# LEDdriverSFE_CREE_02.net
KiCad netlist of a schematic drawn in EAGLE
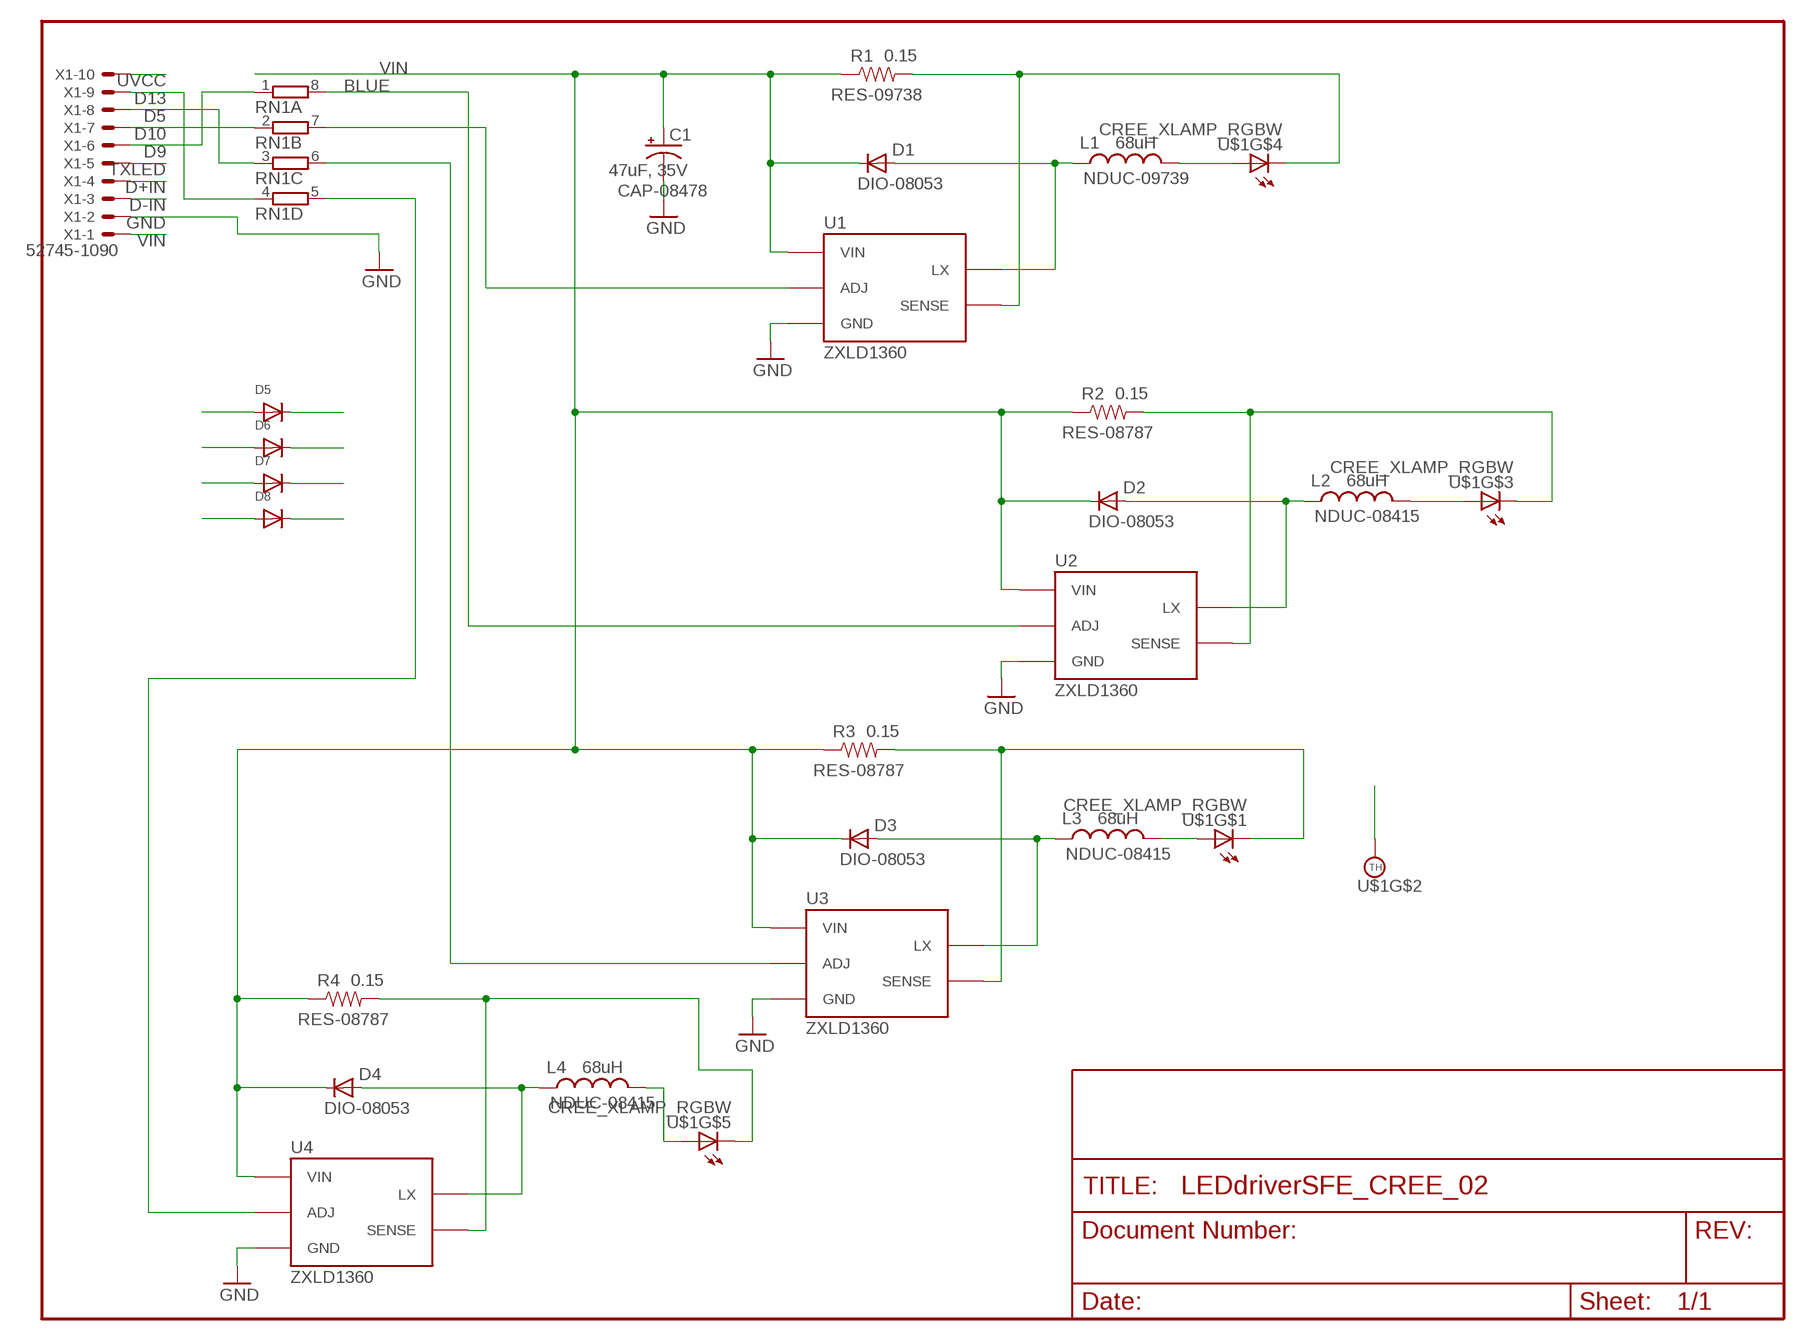
[diagram p0: schematic, sheet 1]

(export (version "E")
  (design (tool "Eeschema 10.0.6"))
  (components
    (comp (ref "C1")
      (value "47uF, 35V")
      (footprint "eagle-import:PANASONIC_D")
      (libsource (lib "eagle-import") (part "CAP_POLD"))
    )
    (comp (ref "D1")
      (value "MBRA140")
      (footprint "eagle-import:SMA-DIODE")
      (libsource (lib "eagle-import") (part "DIODESMA"))
    )
    (comp (ref "D2")
      (value "MBRA140")
      (footprint "eagle-import:SMA-DIODE")
      (libsource (lib "eagle-import") (part "DIODESMA"))
    )
    (comp (ref "D3")
      (value "MBRA140")
      (footprint "eagle-import:SMA-DIODE")
      (libsource (lib "eagle-import") (part "DIODESMA"))
    )
    (comp (ref "D4")
      (value "MBRA140")
      (footprint "eagle-import:SMA-DIODE")
      (libsource (lib "eagle-import") (part "DIODESMA"))
    )
    (comp (ref "D5")
      (value "DIODESOD-323F")
      (footprint "eagle-import:SOD-323F")
      (libsource (lib "eagle-import") (part "DIODESOD-323F"))
    )
    (comp (ref "D6")
      (value "DIODESOD-323F")
      (footprint "eagle-import:SOD-323F")
      (libsource (lib "eagle-import") (part "DIODESOD-323F"))
    )
    (comp (ref "D7")
      (value "DIODESOD-323F")
      (footprint "eagle-import:SOD-323F")
      (libsource (lib "eagle-import") (part "DIODESOD-323F"))
    )
    (comp (ref "D8")
      (value "DIODESOD-323F")
      (footprint "eagle-import:SOD-323F")
      (libsource (lib "eagle-import") (part "DIODESOD-323F"))
    )
    (comp (ref "L1")
      (value "68uH")
      (footprint "eagle-import:TDK6045")
      (libsource (lib "eagle-import") (part "L-US"))
    )
    (comp (ref "L2")
      (value "68uH")
      (footprint "eagle-import:TDK6045")
      (libsource (lib "eagle-import") (part "L-US"))
    )
    (comp (ref "L3")
      (value "68uH")
      (footprint "eagle-import:TDK6045")
      (libsource (lib "eagle-import") (part "L-US"))
    )
    (comp (ref "L4")
      (value "68uH")
      (footprint "eagle-import:TDK6045")
      (libsource (lib "eagle-import") (part "L-US"))
    )
    (comp (ref "R1")
      (value "0.15")
      (footprint "eagle-import:0603-RES")
      (libsource (lib "eagle-import") (part "RESISTOR0603-RES"))
    )
    (comp (ref "R2")
      (value "0.15")
      (footprint "eagle-import:0603-RES")
      (libsource (lib "eagle-import") (part "RESISTOR0603-RES"))
    )
    (comp (ref "R3")
      (value "0.15")
      (footprint "eagle-import:0603-RES")
      (libsource (lib "eagle-import") (part "RESISTOR0603-RES"))
    )
    (comp (ref "R4")
      (value "0.15")
      (footprint "eagle-import:0603-RES")
      (libsource (lib "eagle-import") (part "RESISTOR0603-RES"))
    )
    (comp (ref "RN1")
      (value "4R-NEXBV8V")
      (footprint "eagle-import:EXBV8V")
      (libsource (lib "eagle-import") (part "4R-NEXBV8V"))
    )
    (comp (ref "U$1")
      (value "CREE_XLAMP_RGBW")
      (footprint "eagle-import:CREE_XLAMP_XML")
      (libsource (lib "eagle-import") (part "CREE_XLAMP_RGBW"))
    )
    (comp (ref "U1")
      (value "ZXLD1360")
      (footprint "eagle-import:SOT23-5")
      (libsource (lib "eagle-import") (part "ZXLD1360"))
    )
    (comp (ref "U2")
      (value "ZXLD1360")
      (footprint "eagle-import:SOT23-5")
      (libsource (lib "eagle-import") (part "ZXLD1360"))
    )
    (comp (ref "U3")
      (value "ZXLD1360")
      (footprint "eagle-import:SOT23-5")
      (libsource (lib "eagle-import") (part "ZXLD1360"))
    )
    (comp (ref "U4")
      (value "ZXLD1360")
      (footprint "eagle-import:SOT23-5")
      (libsource (lib "eagle-import") (part "ZXLD1360"))
    )
    (comp (ref "X1")
      (value "52745-1090")
      (footprint "eagle-import:52745-1090")
      (libsource (lib "eagle-import") (part "52745-1090"))
    )
  )
  (nets
    (net (code "1") (name "/BLUE") (class "Default")
      (node (ref "RN1") (pin "8") (pinfunction "2_8") (pintype "passive"))
      (node (ref "U2") (pin "3") (pinfunction "ADJ_3") (pintype "bidirectional"))
    )
    (net (code "2") (name "/D+IN") (class "Default")
      (node (ref "X1") (pin "4") (pinfunction "S_4") (pintype "passive"))
    )
    (net (code "3") (name "/D-IN") (class "Default")
      (node (ref "X1") (pin "3") (pinfunction "S_3") (pintype "passive"))
    )
    (net (code "4") (name "/D5") (class "Default")
      (node (ref "D8") (pin "C") (pinfunction "C_C") (pintype "passive"))
      (node (ref "RN1") (pin "3") (pinfunction "1_3") (pintype "passive"))
      (node (ref "X1") (pin "8") (pinfunction "S_8") (pintype "passive"))
    )
    (net (code "5") (name "/D9") (class "Default")
      (node (ref "D5") (pin "C") (pinfunction "C_C") (pintype "passive"))
      (node (ref "RN1") (pin "1") (pinfunction "1_1") (pintype "passive"))
      (node (ref "X1") (pin "6") (pinfunction "S_6") (pintype "passive"))
    )
    (net (code "6") (name "/D10") (class "Default")
      (node (ref "D6") (pin "C") (pinfunction "C_C") (pintype "passive"))
      (node (ref "RN1") (pin "2") (pinfunction "1_2") (pintype "passive"))
      (node (ref "X1") (pin "7") (pinfunction "S_7") (pintype "passive"))
    )
    (net (code "7") (name "/D13") (class "Default")
      (node (ref "D7") (pin "C") (pinfunction "C_C") (pintype "passive"))
      (node (ref "RN1") (pin "4") (pinfunction "1_4") (pintype "passive"))
      (node (ref "X1") (pin "9") (pinfunction "S_9") (pintype "passive"))
    )
    (net (code "8") (name "/TXLED") (class "Default")
      (node (ref "X1") (pin "5") (pinfunction "S_5") (pintype "passive"))
    )
    (net (code "9") (name "/UVCC") (class "Default")
      (node (ref "X1") (pin "10") (pinfunction "S_10") (pintype "passive"))
    )
    (net (code "10") (name "/VIN") (class "Default")
      (node (ref "C1") (pin "+") (pinfunction "+_+") (pintype "passive"))
      (node (ref "D1") (pin "C") (pinfunction "C_C") (pintype "passive"))
      (node (ref "D2") (pin "C") (pinfunction "C_C") (pintype "passive"))
      (node (ref "D3") (pin "C") (pinfunction "C_C") (pintype "passive"))
      (node (ref "D4") (pin "C") (pinfunction "C_C") (pintype "passive"))
      (node (ref "R1") (pin "1") (pinfunction "1_1") (pintype "passive"))
      (node (ref "R2") (pin "1") (pinfunction "1_1") (pintype "passive"))
      (node (ref "R3") (pin "1") (pinfunction "1_1") (pintype "passive"))
      (node (ref "R4") (pin "1") (pinfunction "1_1") (pintype "passive"))
      (node (ref "U1") (pin "5") (pinfunction "VIN_5") (pintype "bidirectional"))
      (node (ref "U2") (pin "5") (pinfunction "VIN_5") (pintype "bidirectional"))
      (node (ref "U3") (pin "5") (pinfunction "VIN_5") (pintype "bidirectional"))
      (node (ref "U4") (pin "5") (pinfunction "VIN_5") (pintype "bidirectional"))
      (node (ref "X1") (pin "1") (pinfunction "S_1") (pintype "passive"))
    )
    (net (code "11") (name "GND") (class "Default")
      (node (ref "C1") (pin "-") (pinfunction "-_-") (pintype "passive"))
      (node (ref "D5") (pin "A") (pinfunction "A_A") (pintype "passive"))
      (node (ref "D6") (pin "A") (pinfunction "A_A") (pintype "passive"))
      (node (ref "D7") (pin "A") (pinfunction "A_A") (pintype "passive"))
      (node (ref "D8") (pin "A") (pinfunction "A_A") (pintype "passive"))
      (node (ref "U1") (pin "2") (pinfunction "GND_2") (pintype "bidirectional"))
      (node (ref "U2") (pin "2") (pinfunction "GND_2") (pintype "bidirectional"))
      (node (ref "U3") (pin "2") (pinfunction "GND_2") (pintype "bidirectional"))
      (node (ref "U4") (pin "2") (pinfunction "GND_2") (pintype "bidirectional"))
      (node (ref "X1") (pin "2") (pinfunction "S_2") (pintype "passive"))
    )
    (net (code "12") (name "Net-(RN1B-2)") (class "Default")
      (node (ref "RN1") (pin "7") (pinfunction "2_7") (pintype "passive"))
      (node (ref "U1") (pin "3") (pinfunction "ADJ_3") (pintype "bidirectional"))
    )
    (net (code "13") (name "Net-(RN1C-2)") (class "Default")
      (node (ref "RN1") (pin "6") (pinfunction "2_6") (pintype "passive"))
      (node (ref "U3") (pin "3") (pinfunction "ADJ_3") (pintype "bidirectional"))
    )
    (net (code "14") (name "Net-(RN1D-2)") (class "Default")
      (node (ref "RN1") (pin "5") (pinfunction "2_5") (pintype "passive"))
      (node (ref "U4") (pin "3") (pinfunction "ADJ_3") (pintype "bidirectional"))
    )
    (net (code "15") (name "Net-(U$1A-A)") (class "Default")
      (node (ref "L3") (pin "2") (pinfunction "2_2") (pintype "passive"))
      (node (ref "U$1") (pin "1") (pinfunction "A_1") (pintype "passive"))
    )
    (net (code "16") (name "Net-(U$1A-C)") (class "Default")
      (node (ref "R3") (pin "2") (pinfunction "2_2") (pintype "passive"))
      (node (ref "U$1") (pin "8") (pinfunction "C_8") (pintype "passive"))
      (node (ref "U3") (pin "4") (pinfunction "SENSE_4") (pintype "bidirectional"))
    )
    (net (code "17") (name "Net-(U$1C-A)") (class "Default")
      (node (ref "L2") (pin "2") (pinfunction "2_2") (pintype "passive"))
      (node (ref "U$1") (pin "2") (pinfunction "A_2") (pintype "passive"))
    )
    (net (code "18") (name "Net-(U$1C-C)") (class "Default")
      (node (ref "R2") (pin "2") (pinfunction "2_2") (pintype "passive"))
      (node (ref "U$1") (pin "7") (pinfunction "C_7") (pintype "passive"))
      (node (ref "U2") (pin "4") (pinfunction "SENSE_4") (pintype "bidirectional"))
    )
    (net (code "19") (name "Net-(U$1D-A)") (class "Default")
      (node (ref "L1") (pin "2") (pinfunction "2_2") (pintype "passive"))
      (node (ref "U$1") (pin "3") (pinfunction "A_3") (pintype "passive"))
    )
    (net (code "20") (name "Net-(U$1D-C)") (class "Default")
      (node (ref "R1") (pin "2") (pinfunction "2_2") (pintype "passive"))
      (node (ref "U$1") (pin "6") (pinfunction "C_6") (pintype "passive"))
      (node (ref "U1") (pin "4") (pinfunction "SENSE_4") (pintype "bidirectional"))
    )
    (net (code "21") (name "Net-(U$1E-A)") (class "Default")
      (node (ref "L4") (pin "2") (pinfunction "2_2") (pintype "passive"))
      (node (ref "U$1") (pin "4") (pinfunction "A_4") (pintype "passive"))
    )
    (net (code "22") (name "Net-(U$1E-C)") (class "Default")
      (node (ref "R4") (pin "2") (pinfunction "2_2") (pintype "passive"))
      (node (ref "U$1") (pin "5") (pinfunction "C_5") (pintype "passive"))
      (node (ref "U4") (pin "4") (pinfunction "SENSE_4") (pintype "bidirectional"))
    )
    (net (code "23") (name "Net-(U1-LX)") (class "Default")
      (node (ref "D1") (pin "A") (pinfunction "A_A") (pintype "passive"))
      (node (ref "L1") (pin "1") (pinfunction "1_1") (pintype "passive"))
      (node (ref "U1") (pin "1") (pinfunction "LX_1") (pintype "bidirectional"))
    )
    (net (code "24") (name "Net-(U2-LX)") (class "Default")
      (node (ref "D2") (pin "A") (pinfunction "A_A") (pintype "passive"))
      (node (ref "L2") (pin "1") (pinfunction "1_1") (pintype "passive"))
      (node (ref "U2") (pin "1") (pinfunction "LX_1") (pintype "bidirectional"))
    )
    (net (code "25") (name "Net-(U3-LX)") (class "Default")
      (node (ref "D3") (pin "A") (pinfunction "A_A") (pintype "passive"))
      (node (ref "L3") (pin "1") (pinfunction "1_1") (pintype "passive"))
      (node (ref "U3") (pin "1") (pinfunction "LX_1") (pintype "bidirectional"))
    )
    (net (code "26") (name "Net-(U4-LX)") (class "Default")
      (node (ref "D4") (pin "A") (pinfunction "A_A") (pintype "passive"))
      (node (ref "L4") (pin "1") (pinfunction "1_1") (pintype "passive"))
      (node (ref "U4") (pin "1") (pinfunction "LX_1") (pintype "bidirectional"))
    )
    (net (code "27") (name "unconnected-(U$1B-TH-PadP$1)") (class "Default")
      (node (ref "U$1") (pin "P$1") (pinfunction "TH_P$1") (pintype "passive"))
    )
  )
)
